# button.net
KiCad netlist of a schematic drawn in EAGLE
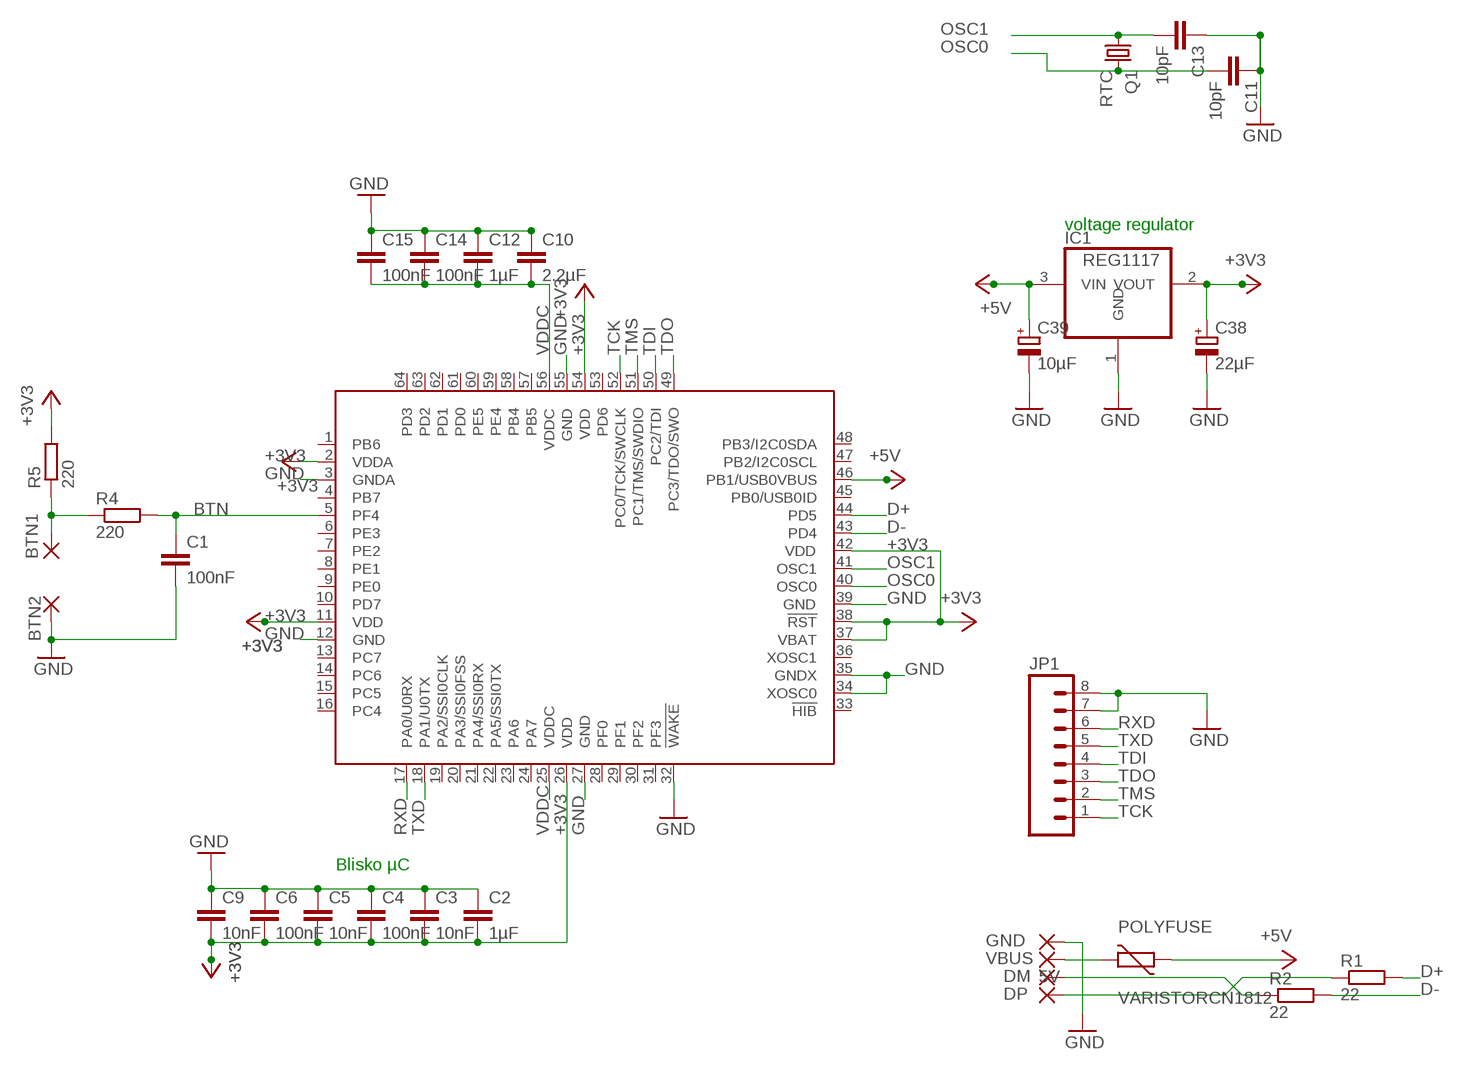
[diagram p0: schematic, sheet 1]

(export (version "E")
  (design (tool "Eeschema 10.0.6"))
  (components
    (comp (ref "BTN1")
      (value "1,6/0,8")
      (footprint "eagle-import:1,6_0,8")
      (libsource (lib "eagle-import") (part "1,6/0,8"))
    )
    (comp (ref "BTN2")
      (value "1,6/0,8")
      (footprint "eagle-import:1,6_0,8")
      (libsource (lib "eagle-import") (part "1,6/0,8"))
    )
    (comp (ref "C1")
      (value "100nF")
      (footprint "eagle-import:C0603")
      (libsource (lib "eagle-import") (part "C-EUC0603"))
    )
    (comp (ref "C2")
      (value "1µF")
      (footprint "eagle-import:C0603")
      (libsource (lib "eagle-import") (part "C-EUC0603"))
    )
    (comp (ref "C3")
      (value "10nF")
      (footprint "eagle-import:C0603")
      (libsource (lib "eagle-import") (part "C-EUC0603"))
    )
    (comp (ref "C4")
      (value "100nF")
      (footprint "eagle-import:C0603")
      (libsource (lib "eagle-import") (part "C-EUC0603"))
    )
    (comp (ref "C5")
      (value "10nF")
      (footprint "eagle-import:C0603")
      (libsource (lib "eagle-import") (part "C-EUC0603"))
    )
    (comp (ref "C6")
      (value "100nF")
      (footprint "eagle-import:C0603")
      (libsource (lib "eagle-import") (part "C-EUC0603"))
    )
    (comp (ref "C9")
      (value "10nF")
      (footprint "eagle-import:C0603")
      (libsource (lib "eagle-import") (part "C-EUC0603"))
    )
    (comp (ref "C10")
      (value "2.2µF")
      (footprint "eagle-import:C0603")
      (libsource (lib "eagle-import") (part "C-EUC0603"))
    )
    (comp (ref "C11")
      (value "10pF")
      (footprint "eagle-import:C0603")
      (libsource (lib "eagle-import") (part "C-EUC0603"))
    )
    (comp (ref "C12")
      (value "1µF")
      (footprint "eagle-import:C0603")
      (libsource (lib "eagle-import") (part "C-EUC0603"))
    )
    (comp (ref "C13")
      (value "10pF")
      (footprint "eagle-import:C0603")
      (libsource (lib "eagle-import") (part "C-EUC0603"))
    )
    (comp (ref "C14")
      (value "100nF")
      (footprint "eagle-import:C0603")
      (libsource (lib "eagle-import") (part "C-EUC0603"))
    )
    (comp (ref "C15")
      (value "100nF")
      (footprint "eagle-import:C0603")
      (libsource (lib "eagle-import") (part "C-EUC0603"))
    )
    (comp (ref "C38")
      (value "22µF")
      (footprint "eagle-import:B_3528-21W")
      (libsource (lib "eagle-import") (part "CPOL-EUB/3528-21W"))
    )
    (comp (ref "C39")
      (value "10µF")
      (footprint "eagle-import:B_3528-21W")
      (libsource (lib "eagle-import") (part "CPOL-EUB/3528-21W"))
    )
    (comp (ref "DM")
      (value "1,6/0,8")
      (footprint "eagle-import:1,6_0,8")
      (libsource (lib "eagle-import") (part "1,6/0,8"))
    )
    (comp (ref "DP")
      (value "1,6/0,8")
      (footprint "eagle-import:1,6_0,8")
      (libsource (lib "eagle-import") (part "1,6/0,8"))
    )
    (comp (ref "GND")
      (value "1,6/0,8")
      (footprint "eagle-import:1,6_0,8")
      (libsource (lib "eagle-import") (part "1,6/0,8"))
    )
    (comp (ref "IC1")
      (value "REG1117")
      (footprint "eagle-import:SOT223")
      (libsource (lib "eagle-import") (part "REG1117"))
    )
    (comp (ref "IC2")
      (value "TM4C123[7,G]XXPM")
      (footprint "eagle-import:PM_S-PQFP-G64")
      (libsource (lib "eagle-import") (part "TM4C123[7,G]XXPM"))
    )
    (comp (ref "JP1")
      (value "M081X08")
      (footprint "eagle-import:1X08")
      (libsource (lib "eagle-import") (part "M081X08"))
    )
    (comp (ref "POLYFUSE")
      (value "VARISTORCN1812")
      (footprint "eagle-import:CT_CN1812")
      (libsource (lib "eagle-import") (part "VARISTORCN1812"))
    )
    (comp (ref "Q1")
      (value "RTC")
      (footprint "eagle-import:HC49_S")
      (libsource (lib "eagle-import") (part "CRYSTALHC49S"))
    )
    (comp (ref "R1")
      (value "22")
      (footprint "eagle-import:R0805")
      (libsource (lib "eagle-import") (part "resistor_R-EU_R0805"))
    )
    (comp (ref "R2")
      (value "22")
      (footprint "eagle-import:R0805")
      (libsource (lib "eagle-import") (part "resistor_R-EU_R0805"))
    )
    (comp (ref "R4")
      (value "220")
      (footprint "eagle-import:R0603")
      (libsource (lib "eagle-import") (part "R-EU_R0603"))
    )
    (comp (ref "R5")
      (value "220")
      (footprint "eagle-import:R0603")
      (libsource (lib "eagle-import") (part "R-EU_R0603"))
    )
    (comp (ref "VBUS")
      (value "5V")
      (footprint "eagle-import:1,6_0,8")
      (libsource (lib "eagle-import") (part "1,6/0,8"))
    )
  )
  (nets
    (net (code "1") (name "+3V3") (class "Default")
      (node (ref "C2") (pin "2") (pinfunction "2_2") (pintype "passive"))
      (node (ref "C3") (pin "2") (pinfunction "2_2") (pintype "passive"))
      (node (ref "C38") (pin "+") (pinfunction "+_+") (pintype "passive"))
      (node (ref "C4") (pin "2") (pinfunction "2_2") (pintype "passive"))
      (node (ref "C5") (pin "2") (pinfunction "2_2") (pintype "passive"))
      (node (ref "C6") (pin "2") (pinfunction "2_2") (pintype "passive"))
      (node (ref "C9") (pin "2") (pinfunction "2_2") (pintype "passive"))
      (node (ref "IC1") (pin "2") (pinfunction "VOUT_2") (pintype "output"))
      (node (ref "IC2") (pin "11") (pinfunction "VDD_11") (pintype "bidirectional"))
      (node (ref "IC2") (pin "2") (pinfunction "VDDA_2") (pintype "bidirectional"))
      (node (ref "IC2") (pin "26") (pinfunction "VDD_26") (pintype "bidirectional"))
      (node (ref "IC2") (pin "37") (pinfunction "VBAT_37") (pintype "bidirectional"))
      (node (ref "IC2") (pin "38") (pinfunction "~{RST}_38") (pintype "bidirectional"))
      (node (ref "IC2") (pin "42") (pinfunction "VDD_42") (pintype "bidirectional"))
      (node (ref "IC2") (pin "54") (pinfunction "VDD_54") (pintype "bidirectional"))
      (node (ref "R5") (pin "2") (pinfunction "2_2") (pintype "passive"))
    )
    (net (code "2") (name "+5V") (class "Default")
      (node (ref "C39") (pin "+") (pinfunction "+_+") (pintype "passive"))
      (node (ref "IC1") (pin "3") (pinfunction "VIN_3") (pintype "input"))
      (node (ref "IC2") (pin "46") (pinfunction "PB1/USB0VBUS_46") (pintype "bidirectional"))
      (node (ref "POLYFUSE") (pin "1") (pinfunction "1_1") (pintype "passive"))
    )
    (net (code "3") (name "/BTN") (class "Default")
      (node (ref "C1") (pin "1") (pinfunction "1_1") (pintype "passive"))
      (node (ref "IC2") (pin "5") (pinfunction "PF4_5") (pintype "bidirectional"))
      (node (ref "R4") (pin "2") (pinfunction "2_2") (pintype "passive"))
    )
    (net (code "4") (name "/D+") (class "Default")
      (node (ref "IC2") (pin "44") (pinfunction "PD5_44") (pintype "bidirectional"))
      (node (ref "R1") (pin "2") (pinfunction "2_2") (pintype "passive"))
    )
    (net (code "5") (name "/D-") (class "Default")
      (node (ref "IC2") (pin "43") (pinfunction "PD4_43") (pintype "bidirectional"))
      (node (ref "R2") (pin "2") (pinfunction "2_2") (pintype "passive"))
    )
    (net (code "6") (name "/OSC0") (class "Default")
      (node (ref "C11") (pin "2") (pinfunction "2_2") (pintype "passive"))
      (node (ref "IC2") (pin "40") (pinfunction "OSC0_40") (pintype "bidirectional"))
      (node (ref "Q1") (pin "2") (pinfunction "2_2") (pintype "passive"))
    )
    (net (code "7") (name "/OSC1") (class "Default")
      (node (ref "C13") (pin "2") (pinfunction "2_2") (pintype "passive"))
      (node (ref "IC2") (pin "41") (pinfunction "OSC1_41") (pintype "bidirectional"))
      (node (ref "Q1") (pin "1") (pinfunction "1_1") (pintype "passive"))
    )
    (net (code "8") (name "/RXD") (class "Default")
      (node (ref "IC2") (pin "17") (pinfunction "PA0/U0RX_17") (pintype "bidirectional"))
      (node (ref "JP1") (pin "6") (pinfunction "6_6") (pintype "passive"))
    )
    (net (code "9") (name "/TCK") (class "Default")
      (node (ref "IC2") (pin "52") (pinfunction "PC0/TCK/SWCLK_52") (pintype "bidirectional"))
      (node (ref "JP1") (pin "1") (pinfunction "1_1") (pintype "passive"))
    )
    (net (code "10") (name "/TDI") (class "Default")
      (node (ref "IC2") (pin "50") (pinfunction "PC2/TDI_50") (pintype "bidirectional"))
      (node (ref "JP1") (pin "4") (pinfunction "4_4") (pintype "passive"))
    )
    (net (code "11") (name "/TDO") (class "Default")
      (node (ref "IC2") (pin "49") (pinfunction "PC3/TDO/SWO_49") (pintype "bidirectional"))
      (node (ref "JP1") (pin "3") (pinfunction "3_3") (pintype "passive"))
    )
    (net (code "12") (name "/TMS") (class "Default")
      (node (ref "IC2") (pin "51") (pinfunction "PC1/TMS/SWDIO_51") (pintype "bidirectional"))
      (node (ref "JP1") (pin "2") (pinfunction "2_2") (pintype "passive"))
    )
    (net (code "13") (name "/TXD") (class "Default")
      (node (ref "IC2") (pin "18") (pinfunction "PA1/U0TX_18") (pintype "bidirectional"))
      (node (ref "JP1") (pin "5") (pinfunction "5_5") (pintype "passive"))
    )
    (net (code "14") (name "/VDDC") (class "Default")
      (node (ref "C10") (pin "2") (pinfunction "2_2") (pintype "passive"))
      (node (ref "C12") (pin "2") (pinfunction "2_2") (pintype "passive"))
      (node (ref "C14") (pin "2") (pinfunction "2_2") (pintype "passive"))
      (node (ref "C15") (pin "2") (pinfunction "2_2") (pintype "passive"))
      (node (ref "IC2") (pin "25") (pinfunction "VDDC_25") (pintype "bidirectional"))
      (node (ref "IC2") (pin "56") (pinfunction "VDDC_56") (pintype "bidirectional"))
    )
    (net (code "15") (name "GND") (class "Default")
      (node (ref "BTN2") (pin "1") (pinfunction "P_1") (pintype "passive"))
      (node (ref "C1") (pin "2") (pinfunction "2_2") (pintype "passive"))
      (node (ref "C10") (pin "1") (pinfunction "1_1") (pintype "passive"))
      (node (ref "C11") (pin "1") (pinfunction "1_1") (pintype "passive"))
      (node (ref "C12") (pin "1") (pinfunction "1_1") (pintype "passive"))
      (node (ref "C13") (pin "1") (pinfunction "1_1") (pintype "passive"))
      (node (ref "C14") (pin "1") (pinfunction "1_1") (pintype "passive"))
      (node (ref "C15") (pin "1") (pinfunction "1_1") (pintype "passive"))
      (node (ref "C2") (pin "1") (pinfunction "1_1") (pintype "passive"))
      (node (ref "C3") (pin "1") (pinfunction "1_1") (pintype "passive"))
      (node (ref "C38") (pin "-") (pinfunction "-_-") (pintype "passive"))
      (node (ref "C39") (pin "-") (pinfunction "-_-") (pintype "passive"))
      (node (ref "C4") (pin "1") (pinfunction "1_1") (pintype "passive"))
      (node (ref "C5") (pin "1") (pinfunction "1_1") (pintype "passive"))
      (node (ref "C6") (pin "1") (pinfunction "1_1") (pintype "passive"))
      (node (ref "C9") (pin "1") (pinfunction "1_1") (pintype "passive"))
      (node (ref "GND") (pin "1") (pinfunction "P_1") (pintype "passive"))
      (node (ref "IC1") (pin "1") (pinfunction "GND_1") (pintype "power_in"))
      (node (ref "IC2") (pin "12") (pinfunction "GND_12") (pintype "bidirectional"))
      (node (ref "IC2") (pin "27") (pinfunction "GND_27") (pintype "bidirectional"))
      (node (ref "IC2") (pin "3") (pinfunction "GNDA_3") (pintype "bidirectional"))
      (node (ref "IC2") (pin "32") (pinfunction "~{WAKE}_32") (pintype "bidirectional"))
      (node (ref "IC2") (pin "34") (pinfunction "XOSC0_34") (pintype "bidirectional"))
      (node (ref "IC2") (pin "35") (pinfunction "GNDX_35") (pintype "bidirectional"))
      (node (ref "IC2") (pin "39") (pinfunction "GND_39") (pintype "bidirectional"))
      (node (ref "IC2") (pin "55") (pinfunction "GND_55") (pintype "bidirectional"))
      (node (ref "JP1") (pin "7") (pinfunction "7_7") (pintype "passive"))
      (node (ref "JP1") (pin "8") (pinfunction "8_8") (pintype "passive"))
    )
    (net (code "16") (name "Net-(BTN1-P)") (class "Default")
      (node (ref "BTN1") (pin "1") (pinfunction "P_1") (pintype "passive"))
      (node (ref "R4") (pin "1") (pinfunction "1_1") (pintype "passive"))
      (node (ref "R5") (pin "1") (pinfunction "1_1") (pintype "passive"))
    )
    (net (code "17") (name "Net-(DM-P)") (class "Default")
      (node (ref "DM") (pin "1") (pinfunction "P_1") (pintype "passive"))
      (node (ref "R2") (pin "1") (pinfunction "1_1") (pintype "passive"))
    )
    (net (code "18") (name "Net-(DP-P)") (class "Default")
      (node (ref "DP") (pin "1") (pinfunction "P_1") (pintype "passive"))
      (node (ref "R1") (pin "1") (pinfunction "1_1") (pintype "passive"))
    )
    (net (code "19") (name "Net-(VBUS-P)") (class "Default")
      (node (ref "POLYFUSE") (pin "2") (pinfunction "2_2") (pintype "passive"))
      (node (ref "VBUS") (pin "1") (pinfunction "P_1") (pintype "passive"))
    )
    (net (code "20") (name "unconnected-(IC2-PA2{slash}SSI0CLK-Pad19)") (class "Default")
      (node (ref "IC2") (pin "19") (pinfunction "PA2/SSI0CLK_19") (pintype "bidirectional"))
    )
    (net (code "21") (name "unconnected-(IC2-PA3{slash}SSI0FSS-Pad20)") (class "Default")
      (node (ref "IC2") (pin "20") (pinfunction "PA3/SSI0FSS_20") (pintype "bidirectional"))
    )
    (net (code "22") (name "unconnected-(IC2-PA4{slash}SSI0RX-Pad21)") (class "Default")
      (node (ref "IC2") (pin "21") (pinfunction "PA4/SSI0RX_21") (pintype "bidirectional"))
    )
    (net (code "23") (name "unconnected-(IC2-PA5{slash}SSI0TX-Pad22)") (class "Default")
      (node (ref "IC2") (pin "22") (pinfunction "PA5/SSI0TX_22") (pintype "bidirectional"))
    )
    (net (code "24") (name "unconnected-(IC2-PA6-Pad23)") (class "Default")
      (node (ref "IC2") (pin "23") (pinfunction "PA6_23") (pintype "bidirectional"))
    )
    (net (code "25") (name "unconnected-(IC2-PA7-Pad24)") (class "Default")
      (node (ref "IC2") (pin "24") (pinfunction "PA7_24") (pintype "bidirectional"))
    )
    (net (code "26") (name "unconnected-(IC2-PB0{slash}USB0ID-Pad45)") (class "Default")
      (node (ref "IC2") (pin "45") (pinfunction "PB0/USB0ID_45") (pintype "bidirectional"))
    )
    (net (code "27") (name "unconnected-(IC2-PB2{slash}I2C0SCL-Pad47)") (class "Default")
      (node (ref "IC2") (pin "47") (pinfunction "PB2/I2C0SCL_47") (pintype "bidirectional"))
    )
    (net (code "28") (name "unconnected-(IC2-PB3{slash}I2C0SDA-Pad48)") (class "Default")
      (node (ref "IC2") (pin "48") (pinfunction "PB3/I2C0SDA_48") (pintype "bidirectional"))
    )
    (net (code "29") (name "unconnected-(IC2-PB4-Pad58)") (class "Default")
      (node (ref "IC2") (pin "58") (pinfunction "PB4_58") (pintype "bidirectional"))
    )
    (net (code "30") (name "unconnected-(IC2-PB5-Pad57)") (class "Default")
      (node (ref "IC2") (pin "57") (pinfunction "PB5_57") (pintype "bidirectional"))
    )
    (net (code "31") (name "unconnected-(IC2-PB6-Pad1)") (class "Default")
      (node (ref "IC2") (pin "1") (pinfunction "PB6_1") (pintype "bidirectional"))
    )
    (net (code "32") (name "unconnected-(IC2-PB7-Pad4)") (class "Default")
      (node (ref "IC2") (pin "4") (pinfunction "PB7_4") (pintype "bidirectional"))
    )
    (net (code "33") (name "unconnected-(IC2-PC4-Pad16)") (class "Default")
      (node (ref "IC2") (pin "16") (pinfunction "PC4_16") (pintype "bidirectional"))
    )
    (net (code "34") (name "unconnected-(IC2-PC5-Pad15)") (class "Default")
      (node (ref "IC2") (pin "15") (pinfunction "PC5_15") (pintype "bidirectional"))
    )
    (net (code "35") (name "unconnected-(IC2-PC6-Pad14)") (class "Default")
      (node (ref "IC2") (pin "14") (pinfunction "PC6_14") (pintype "bidirectional"))
    )
    (net (code "36") (name "unconnected-(IC2-PC7-Pad13)") (class "Default")
      (node (ref "IC2") (pin "13") (pinfunction "PC7_13") (pintype "bidirectional"))
    )
    (net (code "37") (name "unconnected-(IC2-PD0-Pad61)") (class "Default")
      (node (ref "IC2") (pin "61") (pinfunction "PD0_61") (pintype "bidirectional"))
    )
    (net (code "38") (name "unconnected-(IC2-PD1-Pad62)") (class "Default")
      (node (ref "IC2") (pin "62") (pinfunction "PD1_62") (pintype "bidirectional"))
    )
    (net (code "39") (name "unconnected-(IC2-PD2-Pad63)") (class "Default")
      (node (ref "IC2") (pin "63") (pinfunction "PD2_63") (pintype "bidirectional"))
    )
    (net (code "40") (name "unconnected-(IC2-PD3-Pad64)") (class "Default")
      (node (ref "IC2") (pin "64") (pinfunction "PD3_64") (pintype "bidirectional"))
    )
    (net (code "41") (name "unconnected-(IC2-PD6-Pad53)") (class "Default")
      (node (ref "IC2") (pin "53") (pinfunction "PD6_53") (pintype "bidirectional"))
    )
    (net (code "42") (name "unconnected-(IC2-PD7-Pad10)") (class "Default")
      (node (ref "IC2") (pin "10") (pinfunction "PD7_10") (pintype "bidirectional"))
    )
    (net (code "43") (name "unconnected-(IC2-PE0-Pad9)") (class "Default")
      (node (ref "IC2") (pin "9") (pinfunction "PE0_9") (pintype "bidirectional"))
    )
    (net (code "44") (name "unconnected-(IC2-PE1-Pad8)") (class "Default")
      (node (ref "IC2") (pin "8") (pinfunction "PE1_8") (pintype "bidirectional"))
    )
    (net (code "45") (name "unconnected-(IC2-PE2-Pad7)") (class "Default")
      (node (ref "IC2") (pin "7") (pinfunction "PE2_7") (pintype "bidirectional"))
    )
    (net (code "46") (name "unconnected-(IC2-PE3-Pad6)") (class "Default")
      (node (ref "IC2") (pin "6") (pinfunction "PE3_6") (pintype "bidirectional"))
    )
    (net (code "47") (name "unconnected-(IC2-PE4-Pad59)") (class "Default")
      (node (ref "IC2") (pin "59") (pinfunction "PE4_59") (pintype "bidirectional"))
    )
    (net (code "48") (name "unconnected-(IC2-PE5-Pad60)") (class "Default")
      (node (ref "IC2") (pin "60") (pinfunction "PE5_60") (pintype "bidirectional"))
    )
    (net (code "49") (name "unconnected-(IC2-PF0-Pad28)") (class "Default")
      (node (ref "IC2") (pin "28") (pinfunction "PF0_28") (pintype "bidirectional"))
    )
    (net (code "50") (name "unconnected-(IC2-PF1-Pad29)") (class "Default")
      (node (ref "IC2") (pin "29") (pinfunction "PF1_29") (pintype "bidirectional"))
    )
    (net (code "51") (name "unconnected-(IC2-PF2-Pad30)") (class "Default")
      (node (ref "IC2") (pin "30") (pinfunction "PF2_30") (pintype "bidirectional"))
    )
    (net (code "52") (name "unconnected-(IC2-PF3-Pad31)") (class "Default")
      (node (ref "IC2") (pin "31") (pinfunction "PF3_31") (pintype "bidirectional"))
    )
    (net (code "53") (name "unconnected-(IC2-XOSC1-Pad36)") (class "Default")
      (node (ref "IC2") (pin "36") (pinfunction "XOSC1_36") (pintype "bidirectional"))
    )
    (net (code "54") (name "unconnected-(IC2-~{HIB}-Pad33)") (class "Default")
      (node (ref "IC2") (pin "33") (pinfunction "~{HIB}_33") (pintype "bidirectional"))
    )
  )
)
